# AD7606_Core.net
KiCad netlist of a schematic drawn in Altium Designer
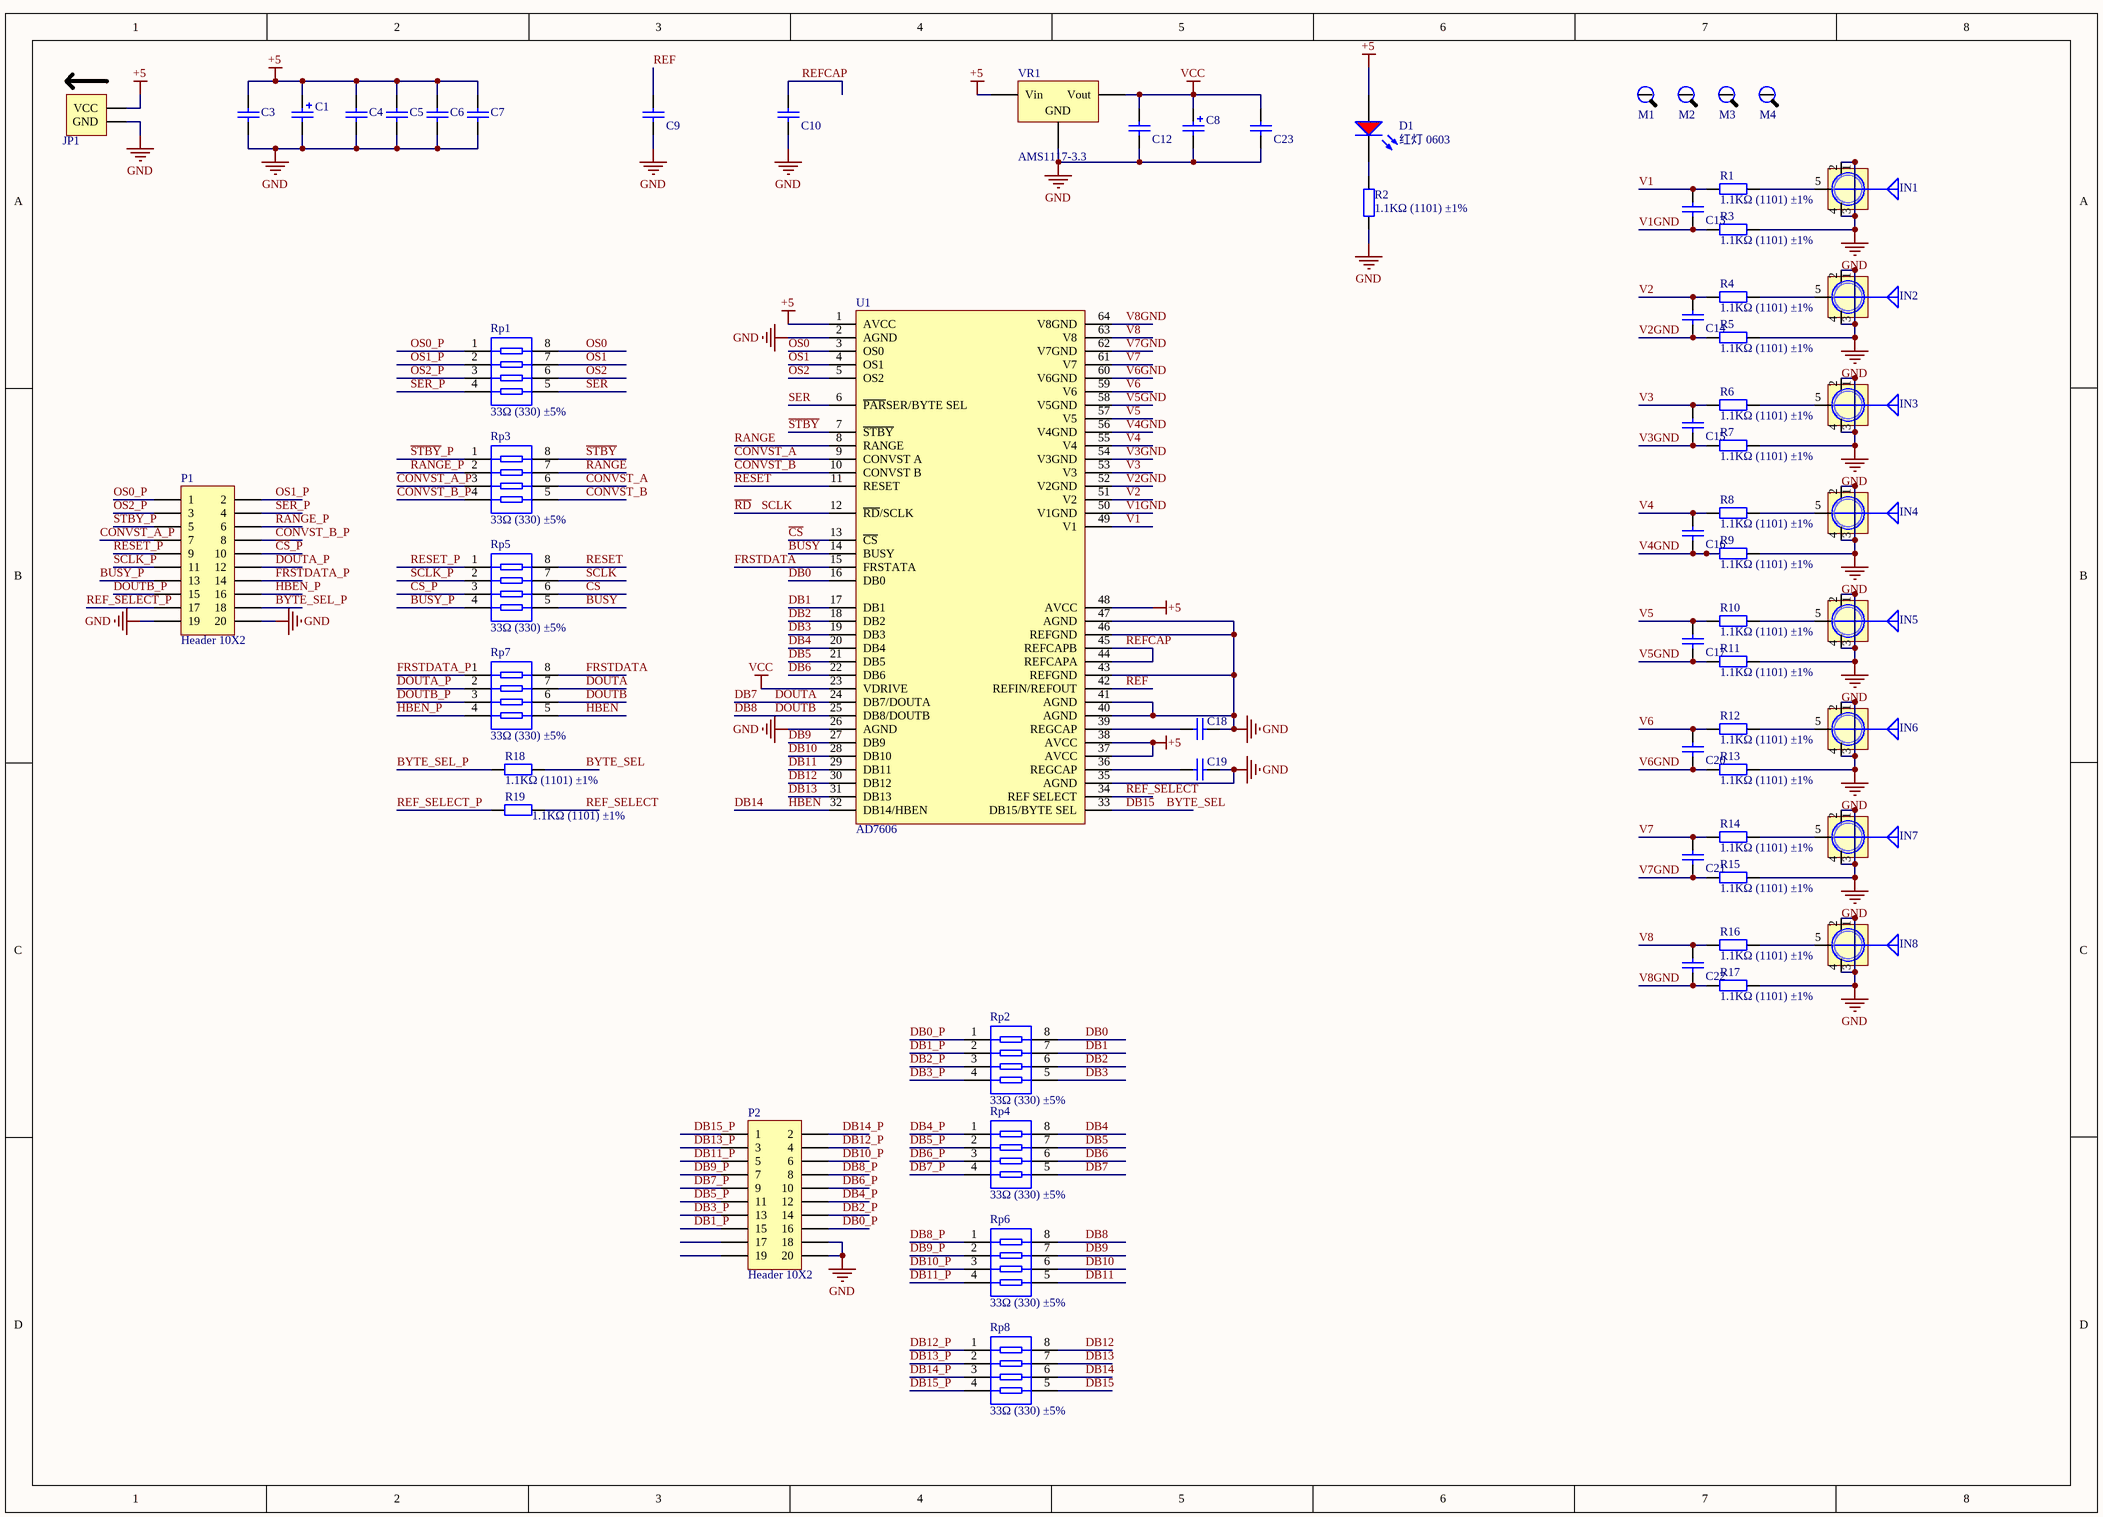
[diagram p0: AD7606_Core.SchDoc]

(export (version "E")
  (design (tool "Eeschema 10.0.6"))
  (components
    (comp (ref "C1")
      (value "10uF (106) ±10% 16V")
      (footprint "CASE-A_3216")
      (description "钽电容")
      (libsource (lib "JLC") (part "3216 10uF (106) 10% 16V"))
    )
    (comp (ref "C3")
      (value "100nF (104) 10% 50V")
      (footprint "0603_C")
      (description "贴片电容")
      (libsource (lib "JLC") (part "0603 100nF (104) 10% 50V"))
    )
    (comp (ref "C4")
      (value "100nF (104) 10% 50V")
      (footprint "0603_C")
      (description "贴片电容")
      (libsource (lib "JLC") (part "0603 100nF (104) 10% 50V"))
    )
    (comp (ref "C5")
      (value "100nF (104) 10% 50V")
      (footprint "0603_C")
      (description "贴片电容")
      (libsource (lib "JLC") (part "0603 100nF (104) 10% 50V"))
    )
    (comp (ref "C6")
      (value "100nF (104) 10% 50V")
      (footprint "0603_C")
      (description "贴片电容")
      (libsource (lib "JLC") (part "0603 100nF (104) 10% 50V"))
    )
    (comp (ref "C7")
      (value "100nF (104) 10% 50V")
      (footprint "0603_C")
      (description "贴片电容")
      (libsource (lib "JLC") (part "0603 100nF (104) 10% 50V"))
    )
    (comp (ref "C8")
      (value "10uF (106) ±10% 16V")
      (footprint "CASE-A_3216")
      (description "钽电容")
      (libsource (lib "JLC") (part "3216 10uF (106) 10% 16V"))
    )
    (comp (ref "C9")
      (value "100nF (104) 10% 50V")
      (footprint "0603_C")
      (description "贴片电容")
      (libsource (lib "JLC") (part "0603 100nF (104) 10% 50V"))
    )
    (comp (ref "C10")
      (value "100nF (104) 10% 50V")
      (footprint "0603_C")
      (description "贴片电容")
      (libsource (lib "JLC") (part "0603 100nF (104) 10% 50V"))
    )
    (comp (ref "C12")
      (value "100nF (104) 10% 50V")
      (footprint "0603_C")
      (description "贴片电容")
      (libsource (lib "JLC") (part "0603 100nF (104) 10% 50V"))
    )
    (comp (ref "C13")
      (value "100nF (104) 10% 50V")
      (footprint "0603_C")
      (description "贴片电容")
      (libsource (lib "JLC") (part "0603 100nF (104) 10% 50V"))
    )
    (comp (ref "C14")
      (value "100nF (104) 10% 50V")
      (footprint "0603_C")
      (description "贴片电容")
      (libsource (lib "JLC") (part "0603 100nF (104) 10% 50V"))
    )
    (comp (ref "C15")
      (value "100nF (104) 10% 50V")
      (footprint "0603_C")
      (description "贴片电容")
      (libsource (lib "JLC") (part "0603 100nF (104) 10% 50V"))
    )
    (comp (ref "C16")
      (value "100nF (104) 10% 50V")
      (footprint "0603_C")
      (description "贴片电容")
      (libsource (lib "JLC") (part "0603 100nF (104) 10% 50V"))
    )
    (comp (ref "C17")
      (value "100nF (104) 10% 50V")
      (footprint "0603_C")
      (description "贴片电容")
      (libsource (lib "JLC") (part "0603 100nF (104) 10% 50V"))
    )
    (comp (ref "C18")
      (value "100nF (104) 10% 50V")
      (footprint "0603_C")
      (description "贴片电容")
      (libsource (lib "JLC") (part "0603 100nF (104) 10% 50V"))
    )
    (comp (ref "C19")
      (value "100nF (104) 10% 50V")
      (footprint "0603_C")
      (description "贴片电容")
      (libsource (lib "JLC") (part "0603 100nF (104) 10% 50V"))
    )
    (comp (ref "C20")
      (value "100nF (104) 10% 50V")
      (footprint "0603_C")
      (description "贴片电容")
      (libsource (lib "JLC") (part "0603 100nF (104) 10% 50V"))
    )
    (comp (ref "C21")
      (value "100nF (104) 10% 50V")
      (footprint "0603_C")
      (description "贴片电容")
      (libsource (lib "JLC") (part "0603 100nF (104) 10% 50V"))
    )
    (comp (ref "C22")
      (value "100nF (104) 10% 50V")
      (footprint "0603_C")
      (description "贴片电容")
      (libsource (lib "JLC") (part "0603 100nF (104) 10% 50V"))
    )
    (comp (ref "C23")
      (value "100nF (104) 10% 50V")
      (footprint "0603_C")
      (description "贴片电容")
      (libsource (lib "JLC") (part "0603 100nF (104) 10% 50V"))
    )
    (comp (ref "D1")
      (value "红灯 0603")
      (footprint "0603_LED_S1")
      (description "发光二极管")
      (libsource (lib "JLC") (part "0603 红灯"))
    )
    (comp (ref "IN1")
      (value "SMA WIFI 天线接口")
      (footprint "SMA_L")
      (description "SMA-2.4G射频天线接口")
      (fields (field (name "版权归属") "源创客"))
      (libsource (lib "Cooperation") (part "PORT_SMA_L"))
    )
    (comp (ref "IN2")
      (value "SMA WIFI 天线接口")
      (footprint "SMA_L")
      (description "SMA-2.4G射频天线接口")
      (fields (field (name "版权归属") "源创客"))
      (libsource (lib "Cooperation") (part "PORT_SMA_L"))
    )
    (comp (ref "IN3")
      (value "SMA WIFI 天线接口")
      (footprint "SMA_L")
      (description "SMA-2.4G射频天线接口")
      (fields (field (name "版权归属") "源创客"))
      (libsource (lib "Cooperation") (part "PORT_SMA_L"))
    )
    (comp (ref "IN4")
      (value "SMA WIFI 天线接口")
      (footprint "SMA_L")
      (description "SMA-2.4G射频天线接口")
      (fields (field (name "版权归属") "源创客"))
      (libsource (lib "Cooperation") (part "PORT_SMA_L"))
    )
    (comp (ref "IN5")
      (value "SMA WIFI 天线接口")
      (footprint "SMA_L")
      (description "SMA-2.4G射频天线接口")
      (fields (field (name "版权归属") "源创客"))
      (libsource (lib "Cooperation") (part "PORT_SMA_L"))
    )
    (comp (ref "IN6")
      (value "SMA WIFI 天线接口")
      (footprint "SMA_L")
      (description "SMA-2.4G射频天线接口")
      (fields (field (name "版权归属") "源创客"))
      (libsource (lib "Cooperation") (part "PORT_SMA_L"))
    )
    (comp (ref "IN7")
      (value "SMA WIFI 天线接口")
      (footprint "SMA_L")
      (description "SMA-2.4G射频天线接口")
      (fields (field (name "版权归属") "源创客"))
      (libsource (lib "Cooperation") (part "PORT_SMA_L"))
    )
    (comp (ref "IN8")
      (value "SMA WIFI 天线接口")
      (footprint "SMA_L")
      (description "SMA-2.4G射频天线接口")
      (fields (field (name "版权归属") "源创客"))
      (libsource (lib "Cooperation") (part "PORT_SMA_L"))
    )
    (comp (ref "JP1")
      (value "HDR-1X2")
      (footprint "Power_IN_3.81-2P")
      (description "2P接插件,模块单电源供电口")
      (fields (field (name "版权归属") "源创客"))
      (libsource (lib "Cooperation") (part "PORT_Power_IN2"))
    )
    (comp (ref "M1")
      (value "M3")
      (footprint "M3x10_L")
      (description "螺丝")
      (libsource (lib "Cooperation") (part "ELSE_M3_screw"))
    )
    (comp (ref "M2")
      (value "M3")
      (footprint "M3x10_L")
      (description "螺丝")
      (libsource (lib "Cooperation") (part "ELSE_M3_screw"))
    )
    (comp (ref "M3")
      (value "M3")
      (footprint "M3x10_L")
      (description "螺丝")
      (libsource (lib "Cooperation") (part "ELSE_M3_screw"))
    )
    (comp (ref "M4")
      (value "M3")
      (footprint "M3x10_L")
      (description "螺丝")
      (libsource (lib "Cooperation") (part "ELSE_M3_screw"))
    )
    (comp (ref "P1")
      (value "Header 10X2")
      (footprint "HDR2X10")
      (description "Header, 10-Pin, Dual row")
      (fields (field (name "PUBLISHER") "Altium Limited"))
      (libsource (lib "Miscellaneous Connectors") (part "Header 10X2"))
    )
    (comp (ref "P2")
      (value "Header 10X2")
      (footprint "HDR2X10")
      (description "Header, 10-Pin, Dual row")
      (fields (field (name "PUBLISHER") "Altium Limited"))
      (libsource (lib "Miscellaneous Connectors") (part "Header 10X2"))
    )
    (comp (ref "R1")
      (value "1.1KΩ (1101) ±1%")
      (footprint "0603_R")
      (description "贴片电阻")
      (libsource (lib "JLC") (part "0603 1.1KΩ (1101) 1%"))
    )
    (comp (ref "R2")
      (value "1.1KΩ (1101) ±1%")
      (footprint "0603_R")
      (description "贴片电阻")
      (libsource (lib "") (part "0603 1.1KΩ (1101) 1%_1"))
    )
    (comp (ref "R3")
      (value "1.1KΩ (1101) ±1%")
      (footprint "0603_R")
      (description "贴片电阻")
      (libsource (lib "JLC") (part "0603 1.1KΩ (1101) 1%"))
    )
    (comp (ref "R4")
      (value "1.1KΩ (1101) ±1%")
      (footprint "0603_R")
      (description "贴片电阻")
      (libsource (lib "JLC") (part "0603 1.1KΩ (1101) 1%"))
    )
    (comp (ref "R5")
      (value "1.1KΩ (1101) ±1%")
      (footprint "0603_R")
      (description "贴片电阻")
      (libsource (lib "JLC") (part "0603 1.1KΩ (1101) 1%"))
    )
    (comp (ref "R6")
      (value "1.1KΩ (1101) ±1%")
      (footprint "0603_R")
      (description "贴片电阻")
      (libsource (lib "JLC") (part "0603 1.1KΩ (1101) 1%"))
    )
    (comp (ref "R7")
      (value "1.1KΩ (1101) ±1%")
      (footprint "0603_R")
      (description "贴片电阻")
      (libsource (lib "JLC") (part "0603 1.1KΩ (1101) 1%"))
    )
    (comp (ref "R8")
      (value "1.1KΩ (1101) ±1%")
      (footprint "0603_R")
      (description "贴片电阻")
      (libsource (lib "JLC") (part "0603 1.1KΩ (1101) 1%"))
    )
    (comp (ref "R9")
      (value "1.1KΩ (1101) ±1%")
      (footprint "0603_R")
      (description "贴片电阻")
      (libsource (lib "JLC") (part "0603 1.1KΩ (1101) 1%"))
    )
    (comp (ref "R10")
      (value "1.1KΩ (1101) ±1%")
      (footprint "0603_R")
      (description "贴片电阻")
      (libsource (lib "JLC") (part "0603 1.1KΩ (1101) 1%"))
    )
    (comp (ref "R11")
      (value "1.1KΩ (1101) ±1%")
      (footprint "0603_R")
      (description "贴片电阻")
      (libsource (lib "JLC") (part "0603 1.1KΩ (1101) 1%"))
    )
    (comp (ref "R12")
      (value "1.1KΩ (1101) ±1%")
      (footprint "0603_R")
      (description "贴片电阻")
      (libsource (lib "JLC") (part "0603 1.1KΩ (1101) 1%"))
    )
    (comp (ref "R13")
      (value "1.1KΩ (1101) ±1%")
      (footprint "0603_R")
      (description "贴片电阻")
      (libsource (lib "JLC") (part "0603 1.1KΩ (1101) 1%"))
    )
    (comp (ref "R14")
      (value "1.1KΩ (1101) ±1%")
      (footprint "0603_R")
      (description "贴片电阻")
      (libsource (lib "JLC") (part "0603 1.1KΩ (1101) 1%"))
    )
    (comp (ref "R15")
      (value "1.1KΩ (1101) ±1%")
      (footprint "0603_R")
      (description "贴片电阻")
      (libsource (lib "JLC") (part "0603 1.1KΩ (1101) 1%"))
    )
    (comp (ref "R16")
      (value "1.1KΩ (1101) ±1%")
      (footprint "0603_R")
      (description "贴片电阻")
      (libsource (lib "JLC") (part "0603 1.1KΩ (1101) 1%"))
    )
    (comp (ref "R17")
      (value "1.1KΩ (1101) ±1%")
      (footprint "0603_R")
      (description "贴片电阻")
      (libsource (lib "JLC") (part "0603 1.1KΩ (1101) 1%"))
    )
    (comp (ref "R18")
      (value "1.1KΩ (1101) ±1%")
      (footprint "0603_R")
      (description "贴片电阻")
      (libsource (lib "JLC") (part "0603 1.1KΩ (1101) 1%"))
    )
    (comp (ref "R19")
      (value "1.1KΩ (1101) ±1%")
      (footprint "0603_R")
      (description "贴片电阻")
      (libsource (lib "JLC") (part "0603 1.1KΩ (1101) 1%"))
    )
    (comp (ref "Rp1")
      (value "33Ω (330) ±5%")
      (footprint "0603_Rx4")
      (description "贴片排阻")
      (libsource (lib "JLC") (part "0402*4 33Ω (330) 5%"))
    )
    (comp (ref "Rp2")
      (value "33Ω (330) ±5%")
      (footprint "0603_Rx4")
      (description "贴片排阻")
      (libsource (lib "JLC") (part "0402*4 33Ω (330) 5%"))
    )
    (comp (ref "Rp3")
      (value "33Ω (330) ±5%")
      (footprint "0603_Rx4")
      (description "贴片排阻")
      (libsource (lib "JLC") (part "0402*4 33Ω (330) 5%"))
    )
    (comp (ref "Rp4")
      (value "33Ω (330) ±5%")
      (footprint "0603_Rx4")
      (description "贴片排阻")
      (libsource (lib "JLC") (part "0402*4 33Ω (330) 5%"))
    )
    (comp (ref "Rp5")
      (value "33Ω (330) ±5%")
      (footprint "0603_Rx4")
      (description "贴片排阻")
      (libsource (lib "JLC") (part "0402*4 33Ω (330) 5%"))
    )
    (comp (ref "Rp6")
      (value "33Ω (330) ±5%")
      (footprint "0603_Rx4")
      (description "贴片排阻")
      (libsource (lib "JLC") (part "0402*4 33Ω (330) 5%"))
    )
    (comp (ref "Rp7")
      (value "33Ω (330) ±5%")
      (footprint "0603_Rx4")
      (description "贴片排阻")
      (libsource (lib "JLC") (part "0402*4 33Ω (330) 5%"))
    )
    (comp (ref "Rp8")
      (value "33Ω (330) ±5%")
      (footprint "0603_Rx4")
      (description "贴片排阻")
      (libsource (lib "JLC") (part "0402*4 33Ω (330) 5%"))
    )
    (comp (ref "U1")
      (value "AD7606")
      (footprint "LQFP64 10x10_N")
      (libsource (lib "Cooperation") (part "AD7606"))
    )
    (comp (ref "VR1")
      (value "AMS1117-3.3")
      (footprint "SOT-223")
      (description "低压差线性稳压(LDO)")
      (libsource (lib "JLC") (part "SOT-223 AMS1117-3.3"))
    )
  )
  (nets
    (net (code "1") (name "+5") (class "Default")
      (node (ref "C1") (pin "1") (pinfunction "1_1") (pintype "passive"))
      (node (ref "C3") (pin "2") (pinfunction "2_2") (pintype "passive"))
      (node (ref "C4") (pin "2") (pinfunction "2_2") (pintype "passive"))
      (node (ref "C5") (pin "2") (pinfunction "2_2") (pintype "passive"))
      (node (ref "C6") (pin "2") (pinfunction "2_2") (pintype "passive"))
      (node (ref "C7") (pin "2") (pinfunction "2_2") (pintype "passive"))
      (node (ref "D1") (pin "A") (pinfunction "A_A") (pintype "passive"))
      (node (ref "JP1") (pin "1") (pinfunction "VCC_1") (pintype "passive"))
      (node (ref "U1") (pin "1") (pinfunction "AVCC_1") (pintype "passive"))
      (node (ref "U1") (pin "37") (pinfunction "AVCC_37") (pintype "passive"))
      (node (ref "U1") (pin "38") (pinfunction "AVCC_38") (pintype "passive"))
      (node (ref "U1") (pin "48") (pinfunction "AVCC_48") (pintype "passive"))
      (node (ref "VR1") (pin "3") (pinfunction "Vin_3") (pintype "passive"))
    )
    (net (code "2") (name "/BUSY") (class "Default")
      (node (ref "Rp5") (pin "5") (pinfunction "5_5") (pintype "passive"))
      (node (ref "U1") (pin "14") (pinfunction "BUSY_14") (pintype "passive"))
    )
    (net (code "3") (name "/BUSY_P") (class "Default")
      (node (ref "P1") (pin "13") (pinfunction "13_13") (pintype "passive"))
      (node (ref "Rp5") (pin "4") (pinfunction "4_4") (pintype "passive"))
    )
    (net (code "4") (name "/BYTE_SEL") (class "Default")
      (node (ref "R18") (pin "2") (pinfunction "2_2") (pintype "passive"))
      (node (ref "Rp8") (pin "5") (pinfunction "5_5") (pintype "passive"))
      (node (ref "U1") (pin "33") (pinfunction "DB15/BYTE_SEL_33") (pintype "passive"))
    )
    (net (code "5") (name "/BYTE_SEL_P") (class "Default")
      (node (ref "P1") (pin "18") (pinfunction "18_18") (pintype "passive"))
      (node (ref "R18") (pin "1") (pinfunction "1_1") (pintype "passive"))
    )
    (net (code "6") (name "/CONVST_A") (class "Default")
      (node (ref "Rp3") (pin "6") (pinfunction "6_6") (pintype "passive"))
      (node (ref "U1") (pin "9") (pinfunction "CONVST_A_9") (pintype "passive"))
    )
    (net (code "7") (name "/CONVST_A_P") (class "Default")
      (node (ref "P1") (pin "7") (pinfunction "7_7") (pintype "passive"))
      (node (ref "Rp3") (pin "3") (pinfunction "3_3") (pintype "passive"))
    )
    (net (code "8") (name "/CONVST_B") (class "Default")
      (node (ref "Rp3") (pin "5") (pinfunction "5_5") (pintype "passive"))
      (node (ref "U1") (pin "10") (pinfunction "CONVST_B_10") (pintype "passive"))
    )
    (net (code "9") (name "/CONVST_B_P") (class "Default")
      (node (ref "P1") (pin "8") (pinfunction "8_8") (pintype "passive"))
      (node (ref "Rp3") (pin "4") (pinfunction "4_4") (pintype "passive"))
    )
    (net (code "10") (name "/DB0") (class "Default")
      (node (ref "Rp2") (pin "8") (pinfunction "8_8") (pintype "passive"))
      (node (ref "U1") (pin "16") (pinfunction "DB0_16") (pintype "passive"))
    )
    (net (code "11") (name "/DB0_P") (class "Default")
      (node (ref "P2") (pin "16") (pinfunction "16_16") (pintype "passive"))
      (node (ref "Rp2") (pin "1") (pinfunction "1_1") (pintype "passive"))
    )
    (net (code "12") (name "/DB1") (class "Default")
      (node (ref "Rp2") (pin "7") (pinfunction "7_7") (pintype "passive"))
      (node (ref "U1") (pin "17") (pinfunction "DB1_17") (pintype "passive"))
    )
    (net (code "13") (name "/DB1_P") (class "Default")
      (node (ref "P2") (pin "15") (pinfunction "15_15") (pintype "passive"))
      (node (ref "Rp2") (pin "2") (pinfunction "2_2") (pintype "passive"))
    )
    (net (code "14") (name "/DB2") (class "Default")
      (node (ref "Rp2") (pin "6") (pinfunction "6_6") (pintype "passive"))
      (node (ref "U1") (pin "18") (pinfunction "DB2_18") (pintype "passive"))
    )
    (net (code "15") (name "/DB2_P") (class "Default")
      (node (ref "P2") (pin "14") (pinfunction "14_14") (pintype "passive"))
      (node (ref "Rp2") (pin "3") (pinfunction "3_3") (pintype "passive"))
    )
    (net (code "16") (name "/DB3") (class "Default")
      (node (ref "Rp2") (pin "5") (pinfunction "5_5") (pintype "passive"))
      (node (ref "U1") (pin "19") (pinfunction "DB3_19") (pintype "passive"))
    )
    (net (code "17") (name "/DB3_P") (class "Default")
      (node (ref "P2") (pin "13") (pinfunction "13_13") (pintype "passive"))
      (node (ref "Rp2") (pin "4") (pinfunction "4_4") (pintype "passive"))
    )
    (net (code "18") (name "/DB4") (class "Default")
      (node (ref "Rp4") (pin "8") (pinfunction "8_8") (pintype "passive"))
      (node (ref "U1") (pin "20") (pinfunction "DB4_20") (pintype "passive"))
    )
    (net (code "19") (name "/DB4_P") (class "Default")
      (node (ref "P2") (pin "12") (pinfunction "12_12") (pintype "passive"))
      (node (ref "Rp4") (pin "1") (pinfunction "1_1") (pintype "passive"))
    )
    (net (code "20") (name "/DB5") (class "Default")
      (node (ref "Rp4") (pin "7") (pinfunction "7_7") (pintype "passive"))
      (node (ref "U1") (pin "21") (pinfunction "DB5_21") (pintype "passive"))
    )
    (net (code "21") (name "/DB5_P") (class "Default")
      (node (ref "P2") (pin "11") (pinfunction "11_11") (pintype "passive"))
      (node (ref "Rp4") (pin "2") (pinfunction "2_2") (pintype "passive"))
    )
    (net (code "22") (name "/DB6") (class "Default")
      (node (ref "Rp4") (pin "6") (pinfunction "6_6") (pintype "passive"))
      (node (ref "U1") (pin "22") (pinfunction "DB6_22") (pintype "passive"))
    )
    (net (code "23") (name "/DB6_P") (class "Default")
      (node (ref "P2") (pin "10") (pinfunction "10_10") (pintype "passive"))
      (node (ref "Rp4") (pin "3") (pinfunction "3_3") (pintype "passive"))
    )
    (net (code "24") (name "/DB7") (class "Default")
      (node (ref "Rp4") (pin "5") (pinfunction "5_5") (pintype "passive"))
      (node (ref "Rp7") (pin "7") (pinfunction "7_7") (pintype "passive"))
      (node (ref "U1") (pin "24") (pinfunction "DB7/DOUTA_24") (pintype "passive"))
    )
    (net (code "25") (name "/DB7_P") (class "Default")
      (node (ref "P2") (pin "9") (pinfunction "9_9") (pintype "passive"))
      (node (ref "Rp4") (pin "4") (pinfunction "4_4") (pintype "passive"))
    )
    (net (code "26") (name "/DB8") (class "Default")
      (node (ref "Rp6") (pin "8") (pinfunction "8_8") (pintype "passive"))
      (node (ref "Rp7") (pin "6") (pinfunction "6_6") (pintype "passive"))
      (node (ref "U1") (pin "25") (pinfunction "DB8/DOUTB_25") (pintype "passive"))
    )
    (net (code "27") (name "/DB8_P") (class "Default")
      (node (ref "P2") (pin "8") (pinfunction "8_8") (pintype "passive"))
      (node (ref "Rp6") (pin "1") (pinfunction "1_1") (pintype "passive"))
    )
    (net (code "28") (name "/DB9") (class "Default")
      (node (ref "Rp6") (pin "7") (pinfunction "7_7") (pintype "passive"))
      (node (ref "U1") (pin "27") (pinfunction "DB9_27") (pintype "passive"))
    )
    (net (code "29") (name "/DB9_P") (class "Default")
      (node (ref "P2") (pin "7") (pinfunction "7_7") (pintype "passive"))
      (node (ref "Rp6") (pin "2") (pinfunction "2_2") (pintype "passive"))
    )
    (net (code "30") (name "/DB10") (class "Default")
      (node (ref "Rp6") (pin "6") (pinfunction "6_6") (pintype "passive"))
      (node (ref "U1") (pin "28") (pinfunction "DB10_28") (pintype "passive"))
    )
    (net (code "31") (name "/DB10_P") (class "Default")
      (node (ref "P2") (pin "6") (pinfunction "6_6") (pintype "passive"))
      (node (ref "Rp6") (pin "3") (pinfunction "3_3") (pintype "passive"))
    )
    (net (code "32") (name "/DB11") (class "Default")
      (node (ref "Rp6") (pin "5") (pinfunction "5_5") (pintype "passive"))
      (node (ref "U1") (pin "29") (pinfunction "DB11_29") (pintype "passive"))
    )
    (net (code "33") (name "/DB11_P") (class "Default")
      (node (ref "P2") (pin "5") (pinfunction "5_5") (pintype "passive"))
      (node (ref "Rp6") (pin "4") (pinfunction "4_4") (pintype "passive"))
    )
    (net (code "34") (name "/DB12") (class "Default")
      (node (ref "Rp8") (pin "8") (pinfunction "8_8") (pintype "passive"))
      (node (ref "U1") (pin "30") (pinfunction "DB12_30") (pintype "passive"))
    )
    (net (code "35") (name "/DB12_P") (class "Default")
      (node (ref "P2") (pin "4") (pinfunction "4_4") (pintype "passive"))
      (node (ref "Rp8") (pin "1") (pinfunction "1_1") (pintype "passive"))
    )
    (net (code "36") (name "/DB13") (class "Default")
      (node (ref "Rp8") (pin "7") (pinfunction "7_7") (pintype "passive"))
      (node (ref "U1") (pin "31") (pinfunction "DB13_31") (pintype "passive"))
    )
    (net (code "37") (name "/DB13_P") (class "Default")
      (node (ref "P2") (pin "3") (pinfunction "3_3") (pintype "passive"))
      (node (ref "Rp8") (pin "2") (pinfunction "2_2") (pintype "passive"))
    )
    (net (code "38") (name "/DB14") (class "Default")
      (node (ref "Rp7") (pin "5") (pinfunction "5_5") (pintype "passive"))
      (node (ref "Rp8") (pin "6") (pinfunction "6_6") (pintype "passive"))
      (node (ref "U1") (pin "32") (pinfunction "DB14/HBEN_32") (pintype "passive"))
    )
    (net (code "39") (name "/DB14_P") (class "Default")
      (node (ref "P2") (pin "2") (pinfunction "2_2") (pintype "passive"))
      (node (ref "Rp8") (pin "3") (pinfunction "3_3") (pintype "passive"))
    )
    (net (code "40") (name "/DB15_P") (class "Default")
      (node (ref "P2") (pin "1") (pinfunction "1_1") (pintype "passive"))
      (node (ref "Rp8") (pin "4") (pinfunction "4_4") (pintype "passive"))
    )
    (net (code "41") (name "/DOUTA_P") (class "Default")
      (node (ref "P1") (pin "12") (pinfunction "12_12") (pintype "passive"))
      (node (ref "Rp7") (pin "2") (pinfunction "2_2") (pintype "passive"))
    )
    (net (code "42") (name "/DOUTB_P") (class "Default")
      (node (ref "P1") (pin "15") (pinfunction "15_15") (pintype "passive"))
      (node (ref "Rp7") (pin "3") (pinfunction "3_3") (pintype "passive"))
    )
    (net (code "43") (name "/FRSTDATA") (class "Default")
      (node (ref "Rp7") (pin "8") (pinfunction "8_8") (pintype "passive"))
      (node (ref "U1") (pin "15") (pinfunction "FRSTATA_15") (pintype "passive"))
    )
    (net (code "44") (name "/FRSTDATA_P") (class "Default")
      (node (ref "P1") (pin "14") (pinfunction "14_14") (pintype "passive"))
      (node (ref "Rp7") (pin "1") (pinfunction "1_1") (pintype "passive"))
    )
    (net (code "45") (name "/HBEN_P") (class "Default")
      (node (ref "P1") (pin "16") (pinfunction "16_16") (pintype "passive"))
      (node (ref "Rp7") (pin "4") (pinfunction "4_4") (pintype "passive"))
    )
    (net (code "46") (name "/OS0") (class "Default")
      (node (ref "Rp1") (pin "8") (pinfunction "8_8") (pintype "passive"))
      (node (ref "U1") (pin "3") (pinfunction "OS0_3") (pintype "passive"))
    )
    (net (code "47") (name "/OS0_P") (class "Default")
      (node (ref "P1") (pin "1") (pinfunction "1_1") (pintype "passive"))
      (node (ref "Rp1") (pin "1") (pinfunction "1_1") (pintype "passive"))
    )
    (net (code "48") (name "/OS1") (class "Default")
      (node (ref "Rp1") (pin "7") (pinfunction "7_7") (pintype "passive"))
      (node (ref "U1") (pin "4") (pinfunction "OS1_4") (pintype "passive"))
    )
    (net (code "49") (name "/OS1_P") (class "Default")
      (node (ref "P1") (pin "2") (pinfunction "2_2") (pintype "passive"))
      (node (ref "Rp1") (pin "2") (pinfunction "2_2") (pintype "passive"))
    )
    (net (code "50") (name "/OS2") (class "Default")
      (node (ref "Rp1") (pin "6") (pinfunction "6_6") (pintype "passive"))
      (node (ref "U1") (pin "5") (pinfunction "OS2_5") (pintype "passive"))
    )
    (net (code "51") (name "/OS2_P") (class "Default")
      (node (ref "P1") (pin "3") (pinfunction "3_3") (pintype "passive"))
      (node (ref "Rp1") (pin "3") (pinfunction "3_3") (pintype "passive"))
    )
    (net (code "52") (name "/RANGE") (class "Default")
      (node (ref "Rp3") (pin "7") (pinfunction "7_7") (pintype "passive"))
      (node (ref "U1") (pin "8") (pinfunction "RANGE_8") (pintype "passive"))
    )
    (net (code "53") (name "/RANGE_P") (class "Default")
      (node (ref "P1") (pin "6") (pinfunction "6_6") (pintype "passive"))
      (node (ref "Rp3") (pin "2") (pinfunction "2_2") (pintype "passive"))
    )
    (net (code "54") (name "/REF") (class "Default")
      (node (ref "C9") (pin "1") (pinfunction "1_1") (pintype "passive"))
      (node (ref "U1") (pin "42") (pinfunction "REFIN/REFOUT_42") (pintype "passive"))
    )
    (net (code "55") (name "/REFCAP") (class "Default")
      (node (ref "C10") (pin "1") (pinfunction "1_1") (pintype "passive"))
      (node (ref "U1") (pin "44") (pinfunction "REFCAPA_44") (pintype "passive"))
      (node (ref "U1") (pin "45") (pinfunction "REFCAPB_45") (pintype "passive"))
    )
    (net (code "56") (name "/REF_SELECT") (class "Default")
      (node (ref "R19") (pin "2") (pinfunction "2_2") (pintype "passive"))
      (node (ref "U1") (pin "34") (pinfunction "REF_SELECT_34") (pintype "passive"))
    )
    (net (code "57") (name "/REF_SELECT_P") (class "Default")
      (node (ref "P1") (pin "17") (pinfunction "17_17") (pintype "passive"))
      (node (ref "R19") (pin "1") (pinfunction "1_1") (pintype "passive"))
    )
    (net (code "58") (name "/RESET") (class "Default")
      (node (ref "Rp5") (pin "8") (pinfunction "8_8") (pintype "passive"))
      (node (ref "U1") (pin "11") (pinfunction "RESET_11") (pintype "passive"))
    )
    (net (code "59") (name "/RESET_P") (class "Default")
      (node (ref "P1") (pin "9") (pinfunction "9_9") (pintype "passive"))
      (node (ref "Rp5") (pin "1") (pinfunction "1_1") (pintype "passive"))
    )
    (net (code "60") (name "/SCLK") (class "Default")
      (node (ref "Rp5") (pin "7") (pinfunction "7_7") (pintype "passive"))
      (node (ref "U1") (pin "12") (pinfunction "~{RD}/SCLK_12") (pintype "passive"))
    )
    (net (code "61") (name "/SCLK_P") (class "Default")
      (node (ref "P1") (pin "11") (pinfunction "11_11") (pintype "passive"))
      (node (ref "Rp5") (pin "2") (pinfunction "2_2") (pintype "passive"))
    )
    (net (code "62") (name "/SER") (class "Default")
      (node (ref "Rp1") (pin "5") (pinfunction "5_5") (pintype "passive"))
      (node (ref "U1") (pin "6") (pinfunction "~{PAR}SER/BYTE_SEL_6") (pintype "passive"))
    )
    (net (code "63") (name "/SER_P") (class "Default")
      (node (ref "P1") (pin "4") (pinfunction "4_4") (pintype "passive"))
      (node (ref "Rp1") (pin "4") (pinfunction "4_4") (pintype "passive"))
    )
    (net (code "64") (name "/V1") (class "Default")
      (node (ref "C13") (pin "1") (pinfunction "1_1") (pintype "passive"))
      (node (ref "R1") (pin "1") (pinfunction "1_1") (pintype "passive"))
      (node (ref "U1") (pin "49") (pinfunction "V1_49") (pintype "passive"))
    )
    (net (code "65") (name "/V1GND") (class "Default")
      (node (ref "C13") (pin "2") (pinfunction "2_2") (pintype "passive"))
      (node (ref "R3") (pin "1") (pinfunction "1_1") (pintype "passive"))
      (node (ref "U1") (pin "50") (pinfunction "V1GND_50") (pintype "passive"))
    )
    (net (code "66") (name "/V2") (class "Default")
      (node (ref "C14") (pin "1") (pinfunction "1_1") (pintype "passive"))
      (node (ref "R4") (pin "1") (pinfunction "1_1") (pintype "passive"))
      (node (ref "U1") (pin "51") (pinfunction "V2_51") (pintype "passive"))
    )
    (net (code "67") (name "/V2GND") (class "Default")
      (node (ref "C14") (pin "2") (pinfunction "2_2") (pintype "passive"))
      (node (ref "R5") (pin "1") (pinfunction "1_1") (pintype "passive"))
      (node (ref "U1") (pin "52") (pinfunction "V2GND_52") (pintype "passive"))
    )
    (net (code "68") (name "/V3") (class "Default")
      (node (ref "C15") (pin "1") (pinfunction "1_1") (pintype "passive"))
      (node (ref "R6") (pin "1") (pinfunction "1_1") (pintype "passive"))
      (node (ref "U1") (pin "53") (pinfunction "V3_53") (pintype "passive"))
    )
    (net (code "69") (name "/V3GND") (class "Default")
      (node (ref "C15") (pin "2") (pinfunction "2_2") (pintype "passive"))
      (node (ref "R7") (pin "1") (pinfunction "1_1") (pintype "passive"))
      (node (ref "U1") (pin "54") (pinfunction "V3GND_54") (pintype "passive"))
    )
    (net (code "70") (name "/V4") (class "Default")
      (node (ref "C16") (pin "1") (pinfunction "1_1") (pintype "passive"))
      (node (ref "R8") (pin "1") (pinfunction "1_1") (pintype "passive"))
      (node (ref "U1") (pin "55") (pinfunction "V4_55") (pintype "passive"))
    )
    (net (code "71") (name "/V4GND") (class "Default")
      (node (ref "C16") (pin "2") (pinfunction "2_2") (pintype "passive"))
      (node (ref "R9") (pin "1") (pinfunction "1_1") (pintype "passive"))
      (node (ref "U1") (pin "56") (pinfunction "V4GND_56") (pintype "passive"))
    )
    (net (code "72") (name "/V5") (class "Default")
      (node (ref "C17") (pin "1") (pinfunction "1_1") (pintype "passive"))
      (node (ref "R10") (pin "1") (pinfunction "1_1") (pintype "passive"))
      (node (ref "U1") (pin "57") (pinfunction "V5_57") (pintype "passive"))
    )
    (net (code "73") (name "/V5GND") (class "Default")
      (node (ref "C17") (pin "2") (pinfunction "2_2") (pintype "passive"))
      (node (ref "R11") (pin "1") (pinfunction "1_1") (pintype "passive"))
      (node (ref "U1") (pin "58") (pinfunction "V5GND_58") (pintype "passive"))
    )
    (net (code "74") (name "/V6") (class "Default")
      (node (ref "C20") (pin "1") (pinfunction "1_1") (pintype "passive"))
      (node (ref "R12") (pin "1") (pinfunction "1_1") (pintype "passive"))
      (node (ref "U1") (pin "59") (pinfunction "V6_59") (pintype "passive"))
    )
    (net (code "75") (name "/V6GND") (class "Default")
      (node (ref "C20") (pin "2") (pinfunction "2_2") (pintype "passive"))
      (node (ref "R13") (pin "1") (pinfunction "1_1") (pintype "passive"))
      (node (ref "U1") (pin "60") (pinfunction "V6GND_60") (pintype "passive"))
    )
    (net (code "76") (name "/V7") (class "Default")
      (node (ref "C21") (pin "1") (pinfunction "1_1") (pintype "passive"))
      (node (ref "R14") (pin "1") (pinfunction "1_1") (pintype "passive"))
      (node (ref "U1") (pin "61") (pinfunction "V7_61") (pintype "passive"))
    )
    (net (code "77") (name "/V7GND") (class "Default")
      (node (ref "C21") (pin "2") (pinfunction "2_2") (pintype "passive"))
      (node (ref "R15") (pin "1") (pinfunction "1_1") (pintype "passive"))
      (node (ref "U1") (pin "62") (pinfunction "V7GND_62") (pintype "passive"))
    )
    (net (code "78") (name "/V8") (class "Default")
      (node (ref "C22") (pin "1") (pinfunction "1_1") (pintype "passive"))
      (node (ref "R16") (pin "1") (pinfunction "1_1") (pintype "passive"))
      (node (ref "U1") (pin "63") (pinfunction "V8_63") (pintype "passive"))
    )
    (net (code "79") (name "/V8GND") (class "Default")
      (node (ref "C22") (pin "2") (pinfunction "2_2") (pintype "passive"))
      (node (ref "R17") (pin "1") (pinfunction "1_1") (pintype "passive"))
      (node (ref "U1") (pin "64") (pinfunction "V8GND_64") (pintype "passive"))
    )
    (net (code "80") (name "/~{CS}") (class "Default")
      (node (ref "Rp5") (pin "6") (pinfunction "6_6") (pintype "passive"))
      (node (ref "U1") (pin "13") (pinfunction "~{CS}_13") (pintype "passive"))
    )
    (net (code "81") (name "/~{CS}_P") (class "Default")
      (node (ref "P1") (pin "10") (pinfunction "10_10") (pintype "passive"))
      (node (ref "Rp5") (pin "3") (pinfunction "3_3") (pintype "passive"))
    )
    (net (code "82") (name "/~{STBY}") (class "Default")
      (node (ref "Rp3") (pin "8") (pinfunction "8_8") (pintype "passive"))
      (node (ref "U1") (pin "7") (pinfunction "~{STBY}_7") (pintype "passive"))
    )
    (net (code "83") (name "/~{STBY}_P") (class "Default")
      (node (ref "P1") (pin "5") (pinfunction "5_5") (pintype "passive"))
      (node (ref "Rp3") (pin "1") (pinfunction "1_1") (pintype "passive"))
    )
    (net (code "84") (name "GND") (class "Default")
      (node (ref "C1") (pin "2") (pinfunction "2_2") (pintype "passive"))
      (node (ref "C10") (pin "2") (pinfunction "2_2") (pintype "passive"))
      (node (ref "C12") (pin "2") (pinfunction "2_2") (pintype "passive"))
      (node (ref "C18") (pin "1") (pinfunction "1_1") (pintype "passive"))
      (node (ref "C19") (pin "1") (pinfunction "1_1") (pintype "passive"))
      (node (ref "C23") (pin "2") (pinfunction "2_2") (pintype "passive"))
      (node (ref "C3") (pin "1") (pinfunction "1_1") (pintype "passive"))
      (node (ref "C4") (pin "1") (pinfunction "1_1") (pintype "passive"))
      (node (ref "C5") (pin "1") (pinfunction "1_1") (pintype "passive"))
      (node (ref "C6") (pin "1") (pinfunction "1_1") (pintype "passive"))
      (node (ref "C7") (pin "1") (pinfunction "1_1") (pintype "passive"))
      (node (ref "C8") (pin "2") (pinfunction "2_2") (pintype "passive"))
      (node (ref "C9") (pin "2") (pinfunction "2_2") (pintype "passive"))
      (node (ref "IN1") (pin "1") (pinfunction "GND_1") (pintype "passive"))
      (node (ref "IN1") (pin "2") (pinfunction "GND_2") (pintype "passive"))
      (node (ref "IN1") (pin "3") (pinfunction "GND_3") (pintype "passive"))
      (node (ref "IN1") (pin "4") (pinfunction "GND_4") (pintype "passive"))
      (node (ref "IN2") (pin "1") (pinfunction "GND_1") (pintype "passive"))
      (node (ref "IN2") (pin "2") (pinfunction "GND_2") (pintype "passive"))
      (node (ref "IN2") (pin "3") (pinfunction "GND_3") (pintype "passive"))
      (node (ref "IN2") (pin "4") (pinfunction "GND_4") (pintype "passive"))
      (node (ref "IN3") (pin "1") (pinfunction "GND_1") (pintype "passive"))
      (node (ref "IN3") (pin "2") (pinfunction "GND_2") (pintype "passive"))
      (node (ref "IN3") (pin "3") (pinfunction "GND_3") (pintype "passive"))
      (node (ref "IN3") (pin "4") (pinfunction "GND_4") (pintype "passive"))
      (node (ref "IN4") (pin "1") (pinfunction "GND_1") (pintype "passive"))
      (node (ref "IN4") (pin "2") (pinfunction "GND_2") (pintype "passive"))
      (node (ref "IN4") (pin "3") (pinfunction "GND_3") (pintype "passive"))
      (node (ref "IN4") (pin "4") (pinfunction "GND_4") (pintype "passive"))
      (node (ref "IN5") (pin "1") (pinfunction "GND_1") (pintype "passive"))
      (node (ref "IN5") (pin "2") (pinfunction "GND_2") (pintype "passive"))
      (node (ref "IN5") (pin "3") (pinfunction "GND_3") (pintype "passive"))
      (node (ref "IN5") (pin "4") (pinfunction "GND_4") (pintype "passive"))
      (node (ref "IN6") (pin "1") (pinfunction "GND_1") (pintype "passive"))
      (node (ref "IN6") (pin "2") (pinfunction "GND_2") (pintype "passive"))
      (node (ref "IN6") (pin "3") (pinfunction "GND_3") (pintype "passive"))
      (node (ref "IN6") (pin "4") (pinfunction "GND_4") (pintype "passive"))
      (node (ref "IN7") (pin "1") (pinfunction "GND_1") (pintype "passive"))
      (node (ref "IN7") (pin "2") (pinfunction "GND_2") (pintype "passive"))
      (node (ref "IN7") (pin "3") (pinfunction "GND_3") (pintype "passive"))
      (node (ref "IN7") (pin "4") (pinfunction "GND_4") (pintype "passive"))
      (node (ref "IN8") (pin "1") (pinfunction "GND_1") (pintype "passive"))
      (node (ref "IN8") (pin "2") (pinfunction "GND_2") (pintype "passive"))
      (node (ref "IN8") (pin "3") (pinfunction "GND_3") (pintype "passive"))
      (node (ref "IN8") (pin "4") (pinfunction "GND_4") (pintype "passive"))
      (node (ref "JP1") (pin "2") (pinfunction "GND_2") (pintype "passive"))
      (node (ref "P1") (pin "19") (pinfunction "19_19") (pintype "passive"))
      (node (ref "P1") (pin "20") (pinfunction "20_20") (pintype "passive"))
      (node (ref "P2") (pin "18") (pinfunction "18_18") (pintype "passive"))
      (node (ref "P2") (pin "20") (pinfunction "20_20") (pintype "passive"))
      (node (ref "R11") (pin "2") (pinfunction "2_2") (pintype "passive"))
      (node (ref "R13") (pin "2") (pinfunction "2_2") (pintype "passive"))
      (node (ref "R15") (pin "2") (pinfunction "2_2") (pintype "passive"))
      (node (ref "R17") (pin "2") (pinfunction "2_2") (pintype "passive"))
      (node (ref "R2") (pin "1") (pinfunction "1_1") (pintype "passive"))
      (node (ref "R3") (pin "2") (pinfunction "2_2") (pintype "passive"))
      (node (ref "R5") (pin "2") (pinfunction "2_2") (pintype "passive"))
      (node (ref "R7") (pin "2") (pinfunction "2_2") (pintype "passive"))
      (node (ref "R9") (pin "2") (pinfunction "2_2") (pintype "passive"))
      (node (ref "U1") (pin "2") (pinfunction "AGND_2") (pintype "passive"))
      (node (ref "U1") (pin "26") (pinfunction "AGND_26") (pintype "passive"))
      (node (ref "U1") (pin "35") (pinfunction "AGND_35") (pintype "passive"))
      (node (ref "U1") (pin "40") (pinfunction "AGND_40") (pintype "passive"))
      (node (ref "U1") (pin "41") (pinfunction "AGND_41") (pintype "passive"))
      (node (ref "U1") (pin "43") (pinfunction "REFGND_43") (pintype "passive"))
      (node (ref "U1") (pin "46") (pinfunction "REFGND_46") (pintype "passive"))
      (node (ref "U1") (pin "47") (pinfunction "AGND_47") (pintype "passive"))
      (node (ref "VR1") (pin "1") (pinfunction "GND_1") (pintype "passive"))
    )
    (net (code "85") (name "Net-(C18-Pad2)") (class "Default")
      (node (ref "C18") (pin "2") (pinfunction "2_2") (pintype "passive"))
      (node (ref "U1") (pin "39") (pinfunction "REGCAP_39") (pintype "passive"))
    )
    (net (code "86") (name "Net-(C19-Pad2)") (class "Default")
      (node (ref "C19") (pin "2") (pinfunction "2_2") (pintype "passive"))
      (node (ref "U1") (pin "36") (pinfunction "REGCAP_36") (pintype "passive"))
    )
    (net (code "87") (name "Net-(D1-PadK)") (class "Default")
      (node (ref "D1") (pin "K") (pinfunction "K_K") (pintype "passive"))
      (node (ref "R2") (pin "2") (pinfunction "2_2") (pintype "passive"))
    )
    (net (code "88") (name "Net-(IN1-SINGLE)") (class "Default")
      (node (ref "IN1") (pin "5") (pinfunction "SINGLE_5") (pintype "passive"))
      (node (ref "R1") (pin "2") (pinfunction "2_2") (pintype "passive"))
    )
    (net (code "89") (name "Net-(IN2-SINGLE)") (class "Default")
      (node (ref "IN2") (pin "5") (pinfunction "SINGLE_5") (pintype "passive"))
      (node (ref "R4") (pin "2") (pinfunction "2_2") (pintype "passive"))
    )
    (net (code "90") (name "Net-(IN3-SINGLE)") (class "Default")
      (node (ref "IN3") (pin "5") (pinfunction "SINGLE_5") (pintype "passive"))
      (node (ref "R6") (pin "2") (pinfunction "2_2") (pintype "passive"))
    )
    (net (code "91") (name "Net-(IN4-SINGLE)") (class "Default")
      (node (ref "IN4") (pin "5") (pinfunction "SINGLE_5") (pintype "passive"))
      (node (ref "R8") (pin "2") (pinfunction "2_2") (pintype "passive"))
    )
    (net (code "92") (name "Net-(IN5-SINGLE)") (class "Default")
      (node (ref "IN5") (pin "5") (pinfunction "SINGLE_5") (pintype "passive"))
      (node (ref "R10") (pin "2") (pinfunction "2_2") (pintype "passive"))
    )
    (net (code "93") (name "Net-(IN6-SINGLE)") (class "Default")
      (node (ref "IN6") (pin "5") (pinfunction "SINGLE_5") (pintype "passive"))
      (node (ref "R12") (pin "2") (pinfunction "2_2") (pintype "passive"))
    )
    (net (code "94") (name "Net-(IN7-SINGLE)") (class "Default")
      (node (ref "IN7") (pin "5") (pinfunction "SINGLE_5") (pintype "passive"))
      (node (ref "R14") (pin "2") (pinfunction "2_2") (pintype "passive"))
    )
    (net (code "95") (name "Net-(IN8-SINGLE)") (class "Default")
      (node (ref "IN8") (pin "5") (pinfunction "SINGLE_5") (pintype "passive"))
      (node (ref "R16") (pin "2") (pinfunction "2_2") (pintype "passive"))
    )
    (net (code "96") (name "VCC") (class "Default")
      (node (ref "C12") (pin "1") (pinfunction "1_1") (pintype "passive"))
      (node (ref "C23") (pin "1") (pinfunction "1_1") (pintype "passive"))
      (node (ref "C8") (pin "1") (pinfunction "1_1") (pintype "passive"))
      (node (ref "U1") (pin "23") (pinfunction "VDRIVE_23") (pintype "passive"))
      (node (ref "VR1") (pin "2") (pinfunction "Vout_2") (pintype "passive"))
    )
    (net (code "97") (name "unconnected-(M1-Pad1)") (class "Default")
      (node (ref "M1") (pin "1") (pinfunction "1_1") (pintype "passive"))
    )
    (net (code "98") (name "unconnected-(M2-Pad1)") (class "Default")
      (node (ref "M2") (pin "1") (pinfunction "1_1") (pintype "passive"))
    )
    (net (code "99") (name "unconnected-(M3-Pad1)") (class "Default")
      (node (ref "M3") (pin "1") (pinfunction "1_1") (pintype "passive"))
    )
    (net (code "100") (name "unconnected-(M4-Pad1)") (class "Default")
      (node (ref "M4") (pin "1") (pinfunction "1_1") (pintype "passive"))
    )
    (net (code "101") (name "unconnected-(P2-Pad17)") (class "Default")
      (node (ref "P2") (pin "17") (pinfunction "17_17") (pintype "passive"))
    )
    (net (code "102") (name "unconnected-(P2-Pad19)") (class "Default")
      (node (ref "P2") (pin "19") (pinfunction "19_19") (pintype "passive"))
    )
  )
)
